# capstone.net
KiCad netlist of a schematic drawn in EAGLE
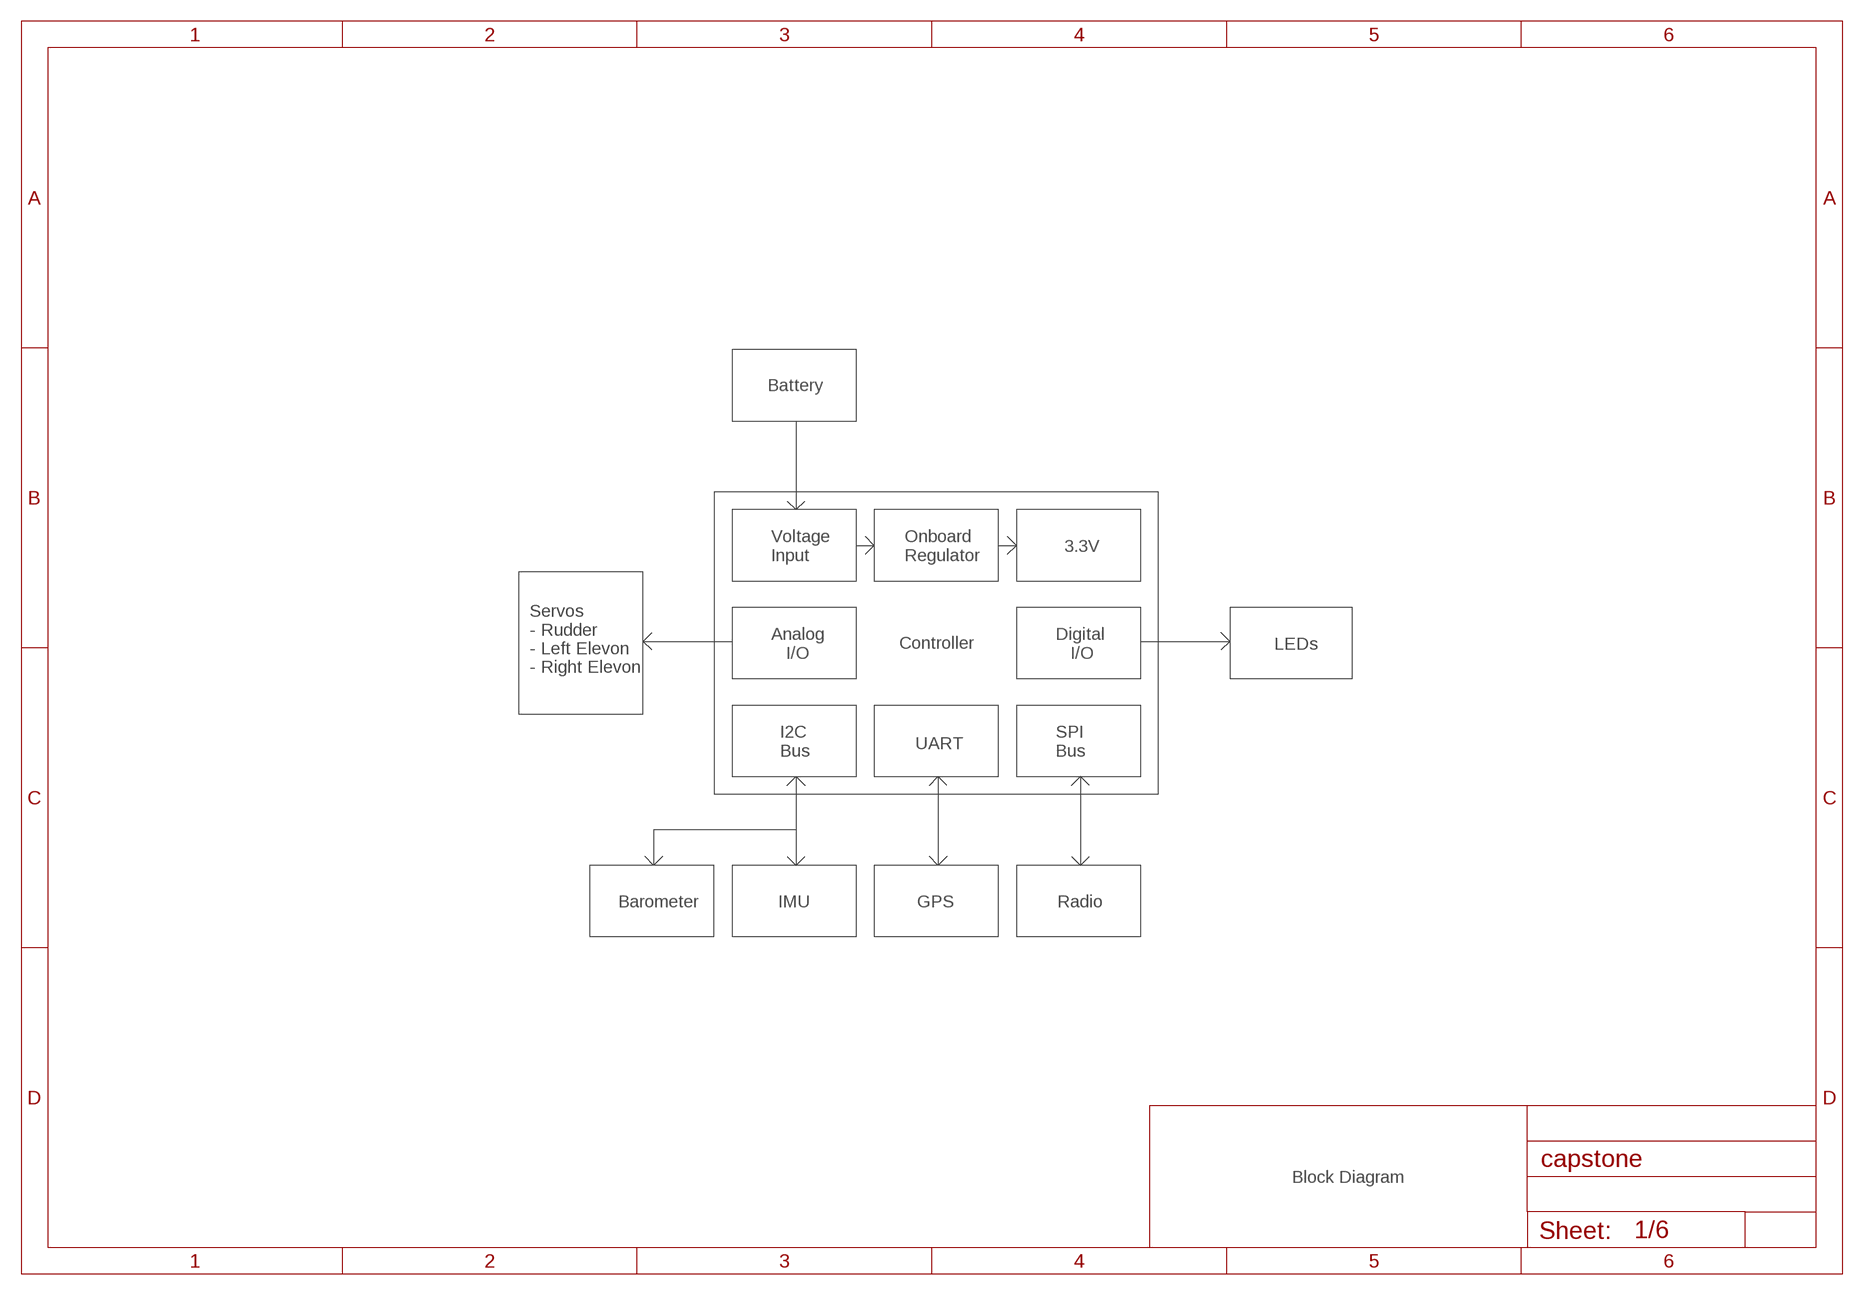
[diagram p0: schematic, sheet 1]
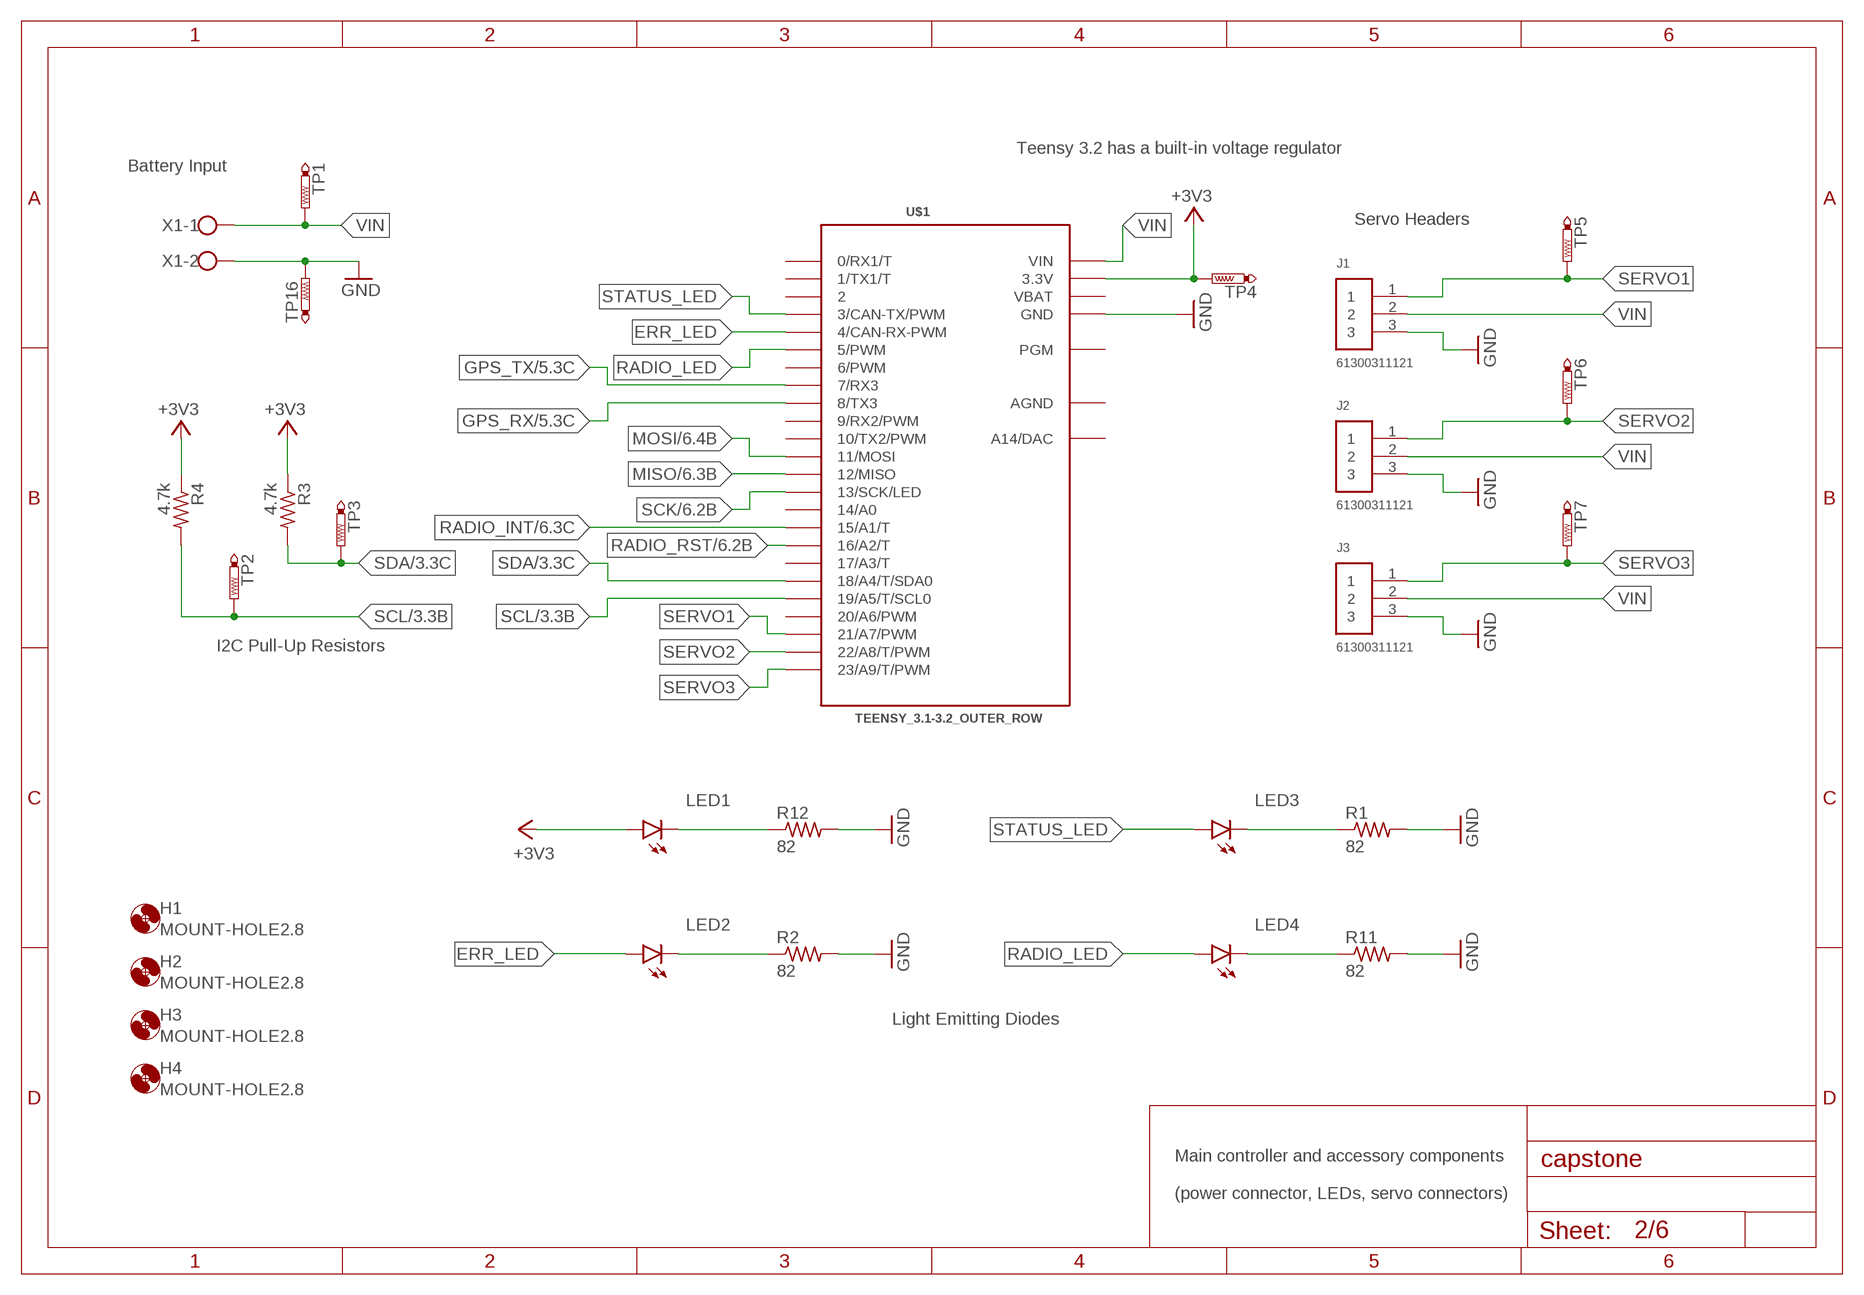
[diagram p1: schematic, sheet 2]
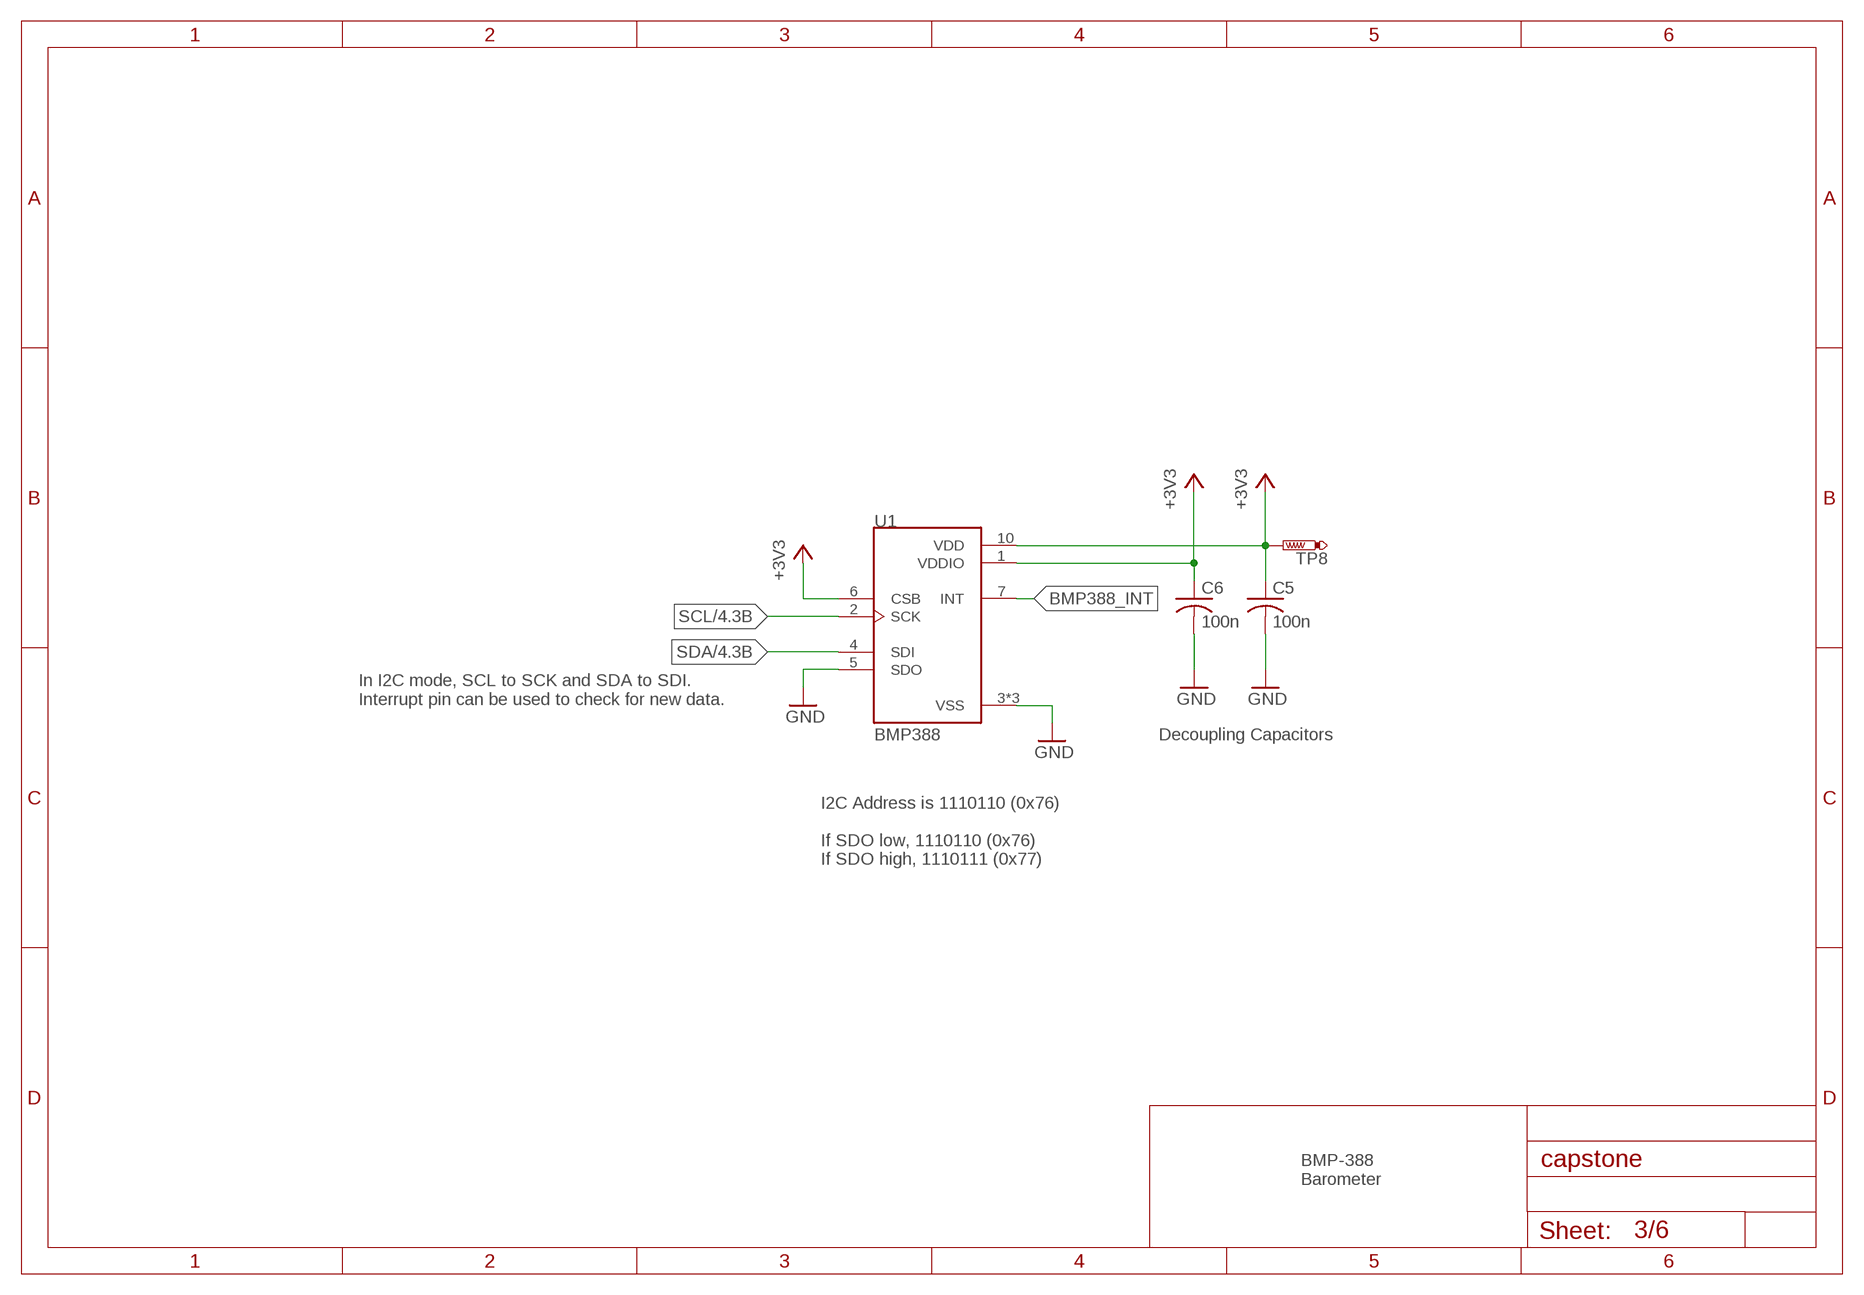
[diagram p2: schematic, sheet 3]
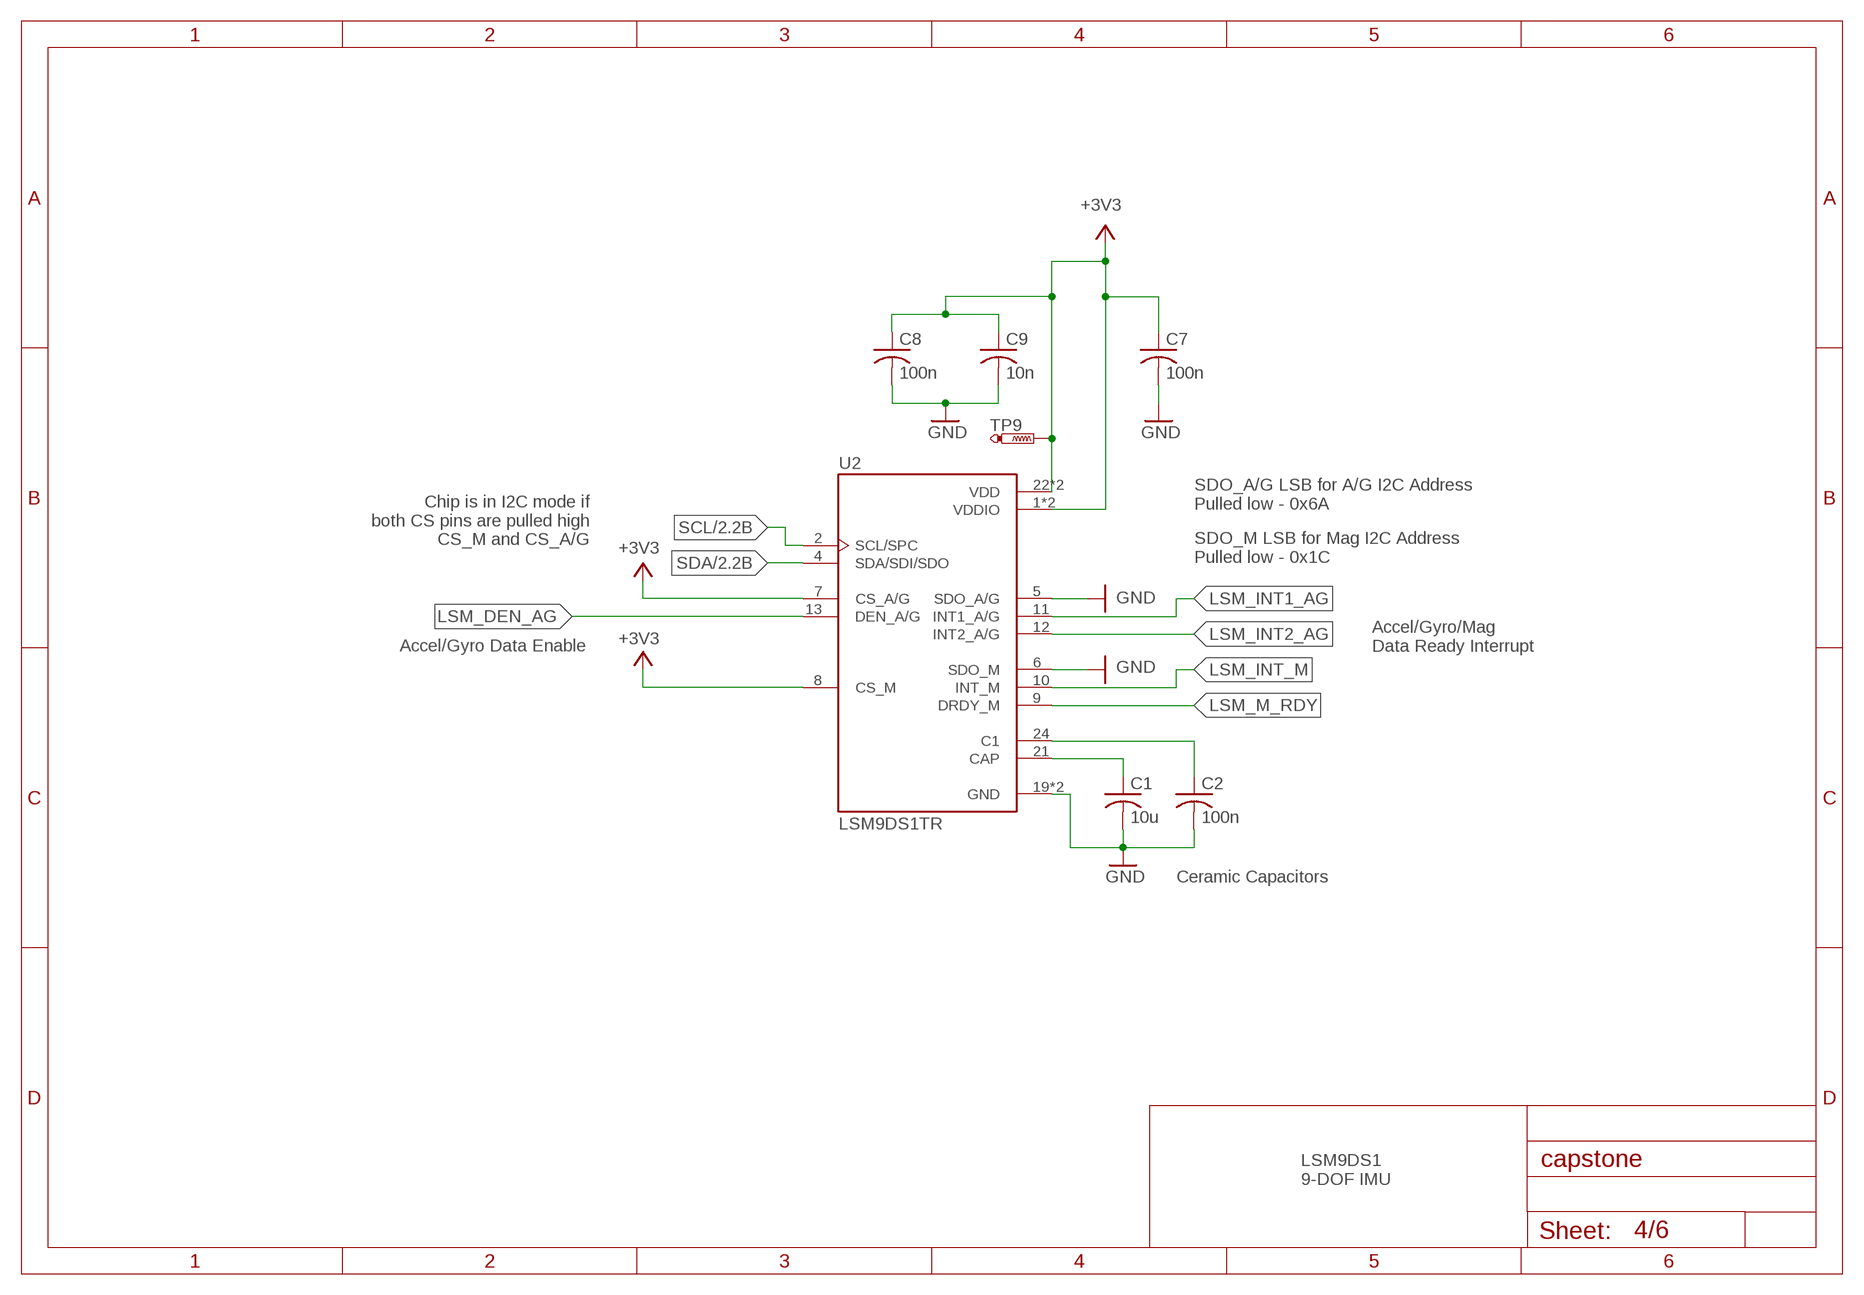
[diagram p3: schematic, sheet 4]
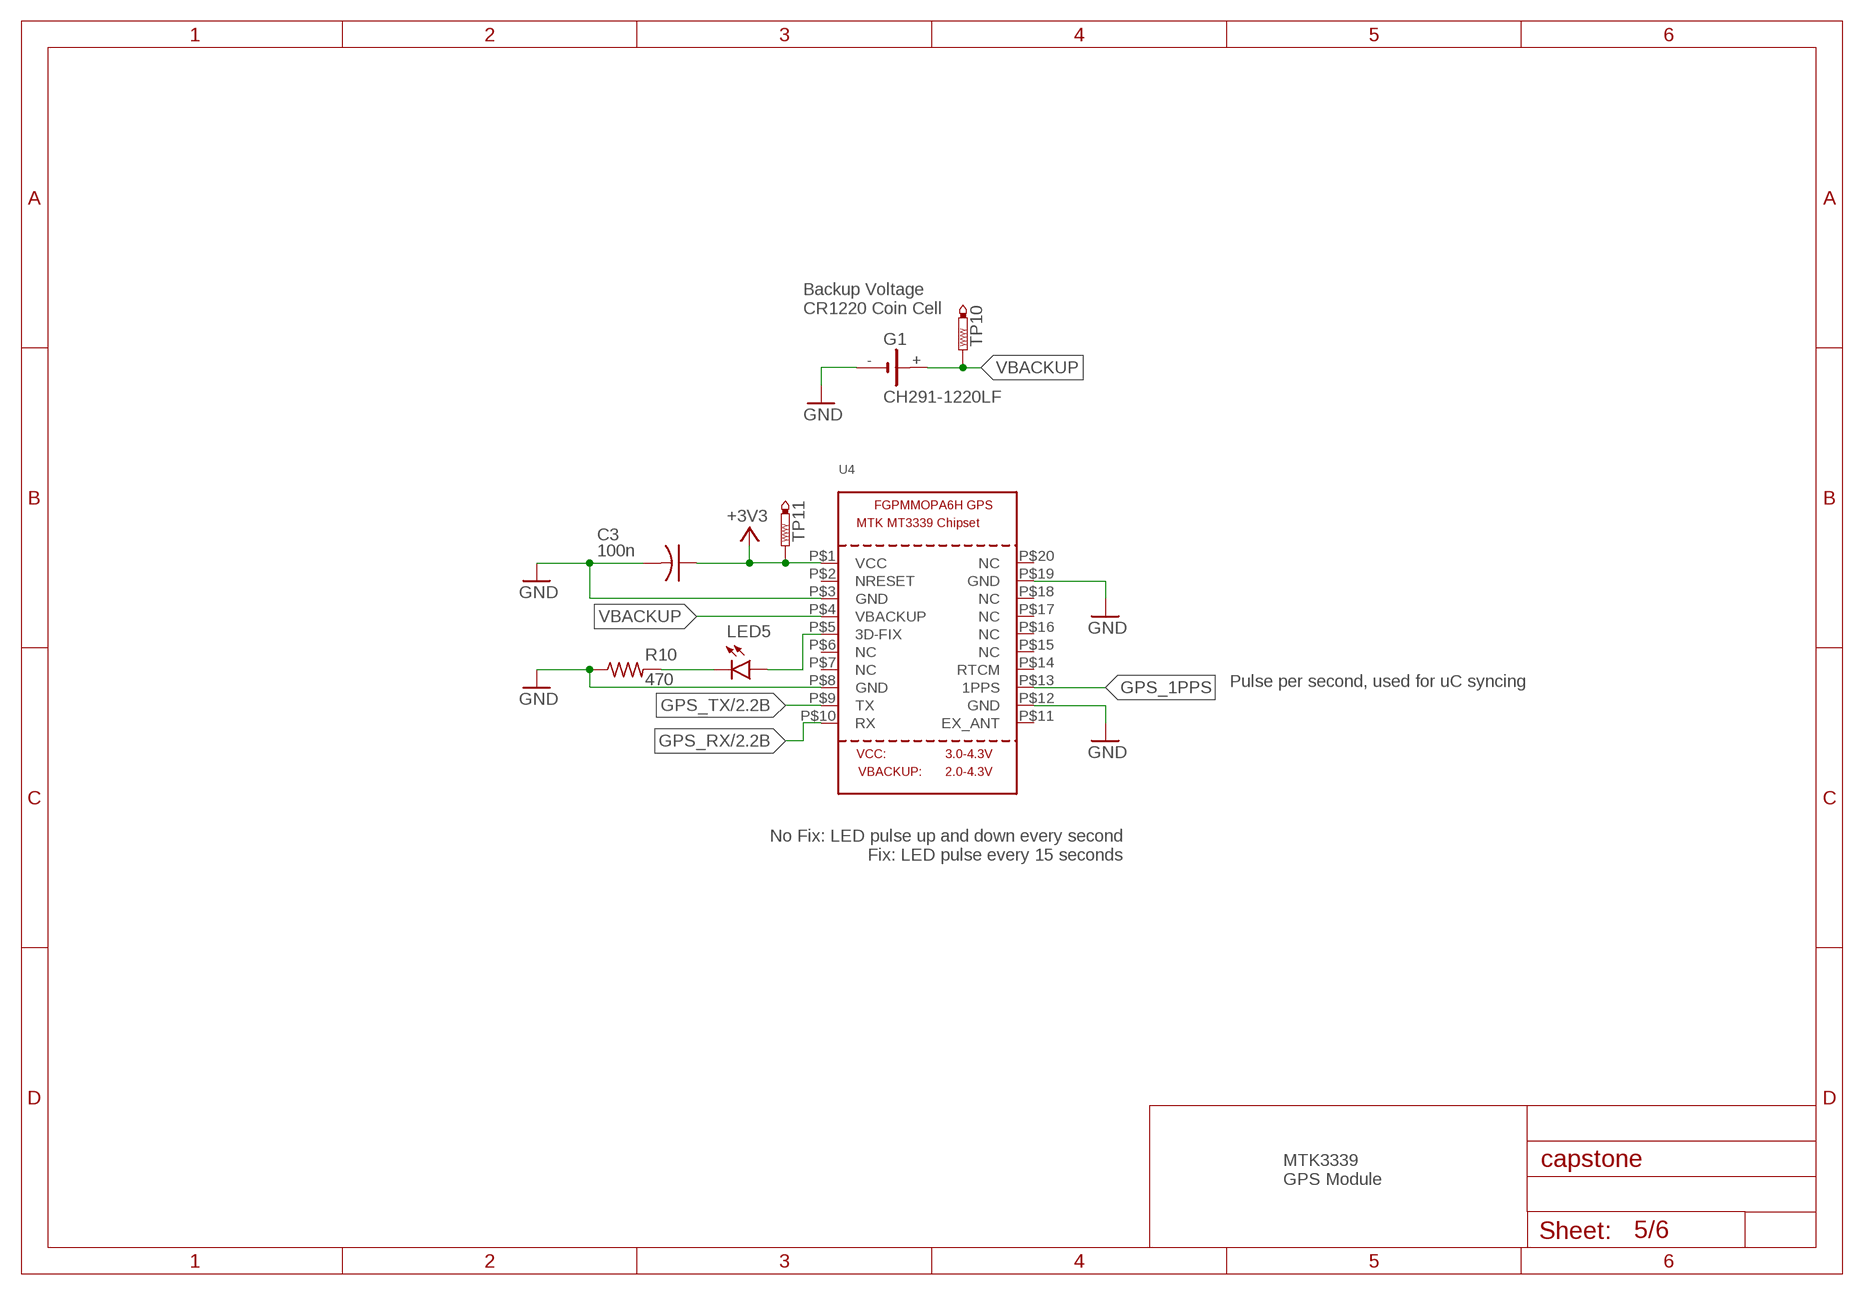
[diagram p4: schematic, sheet 5]
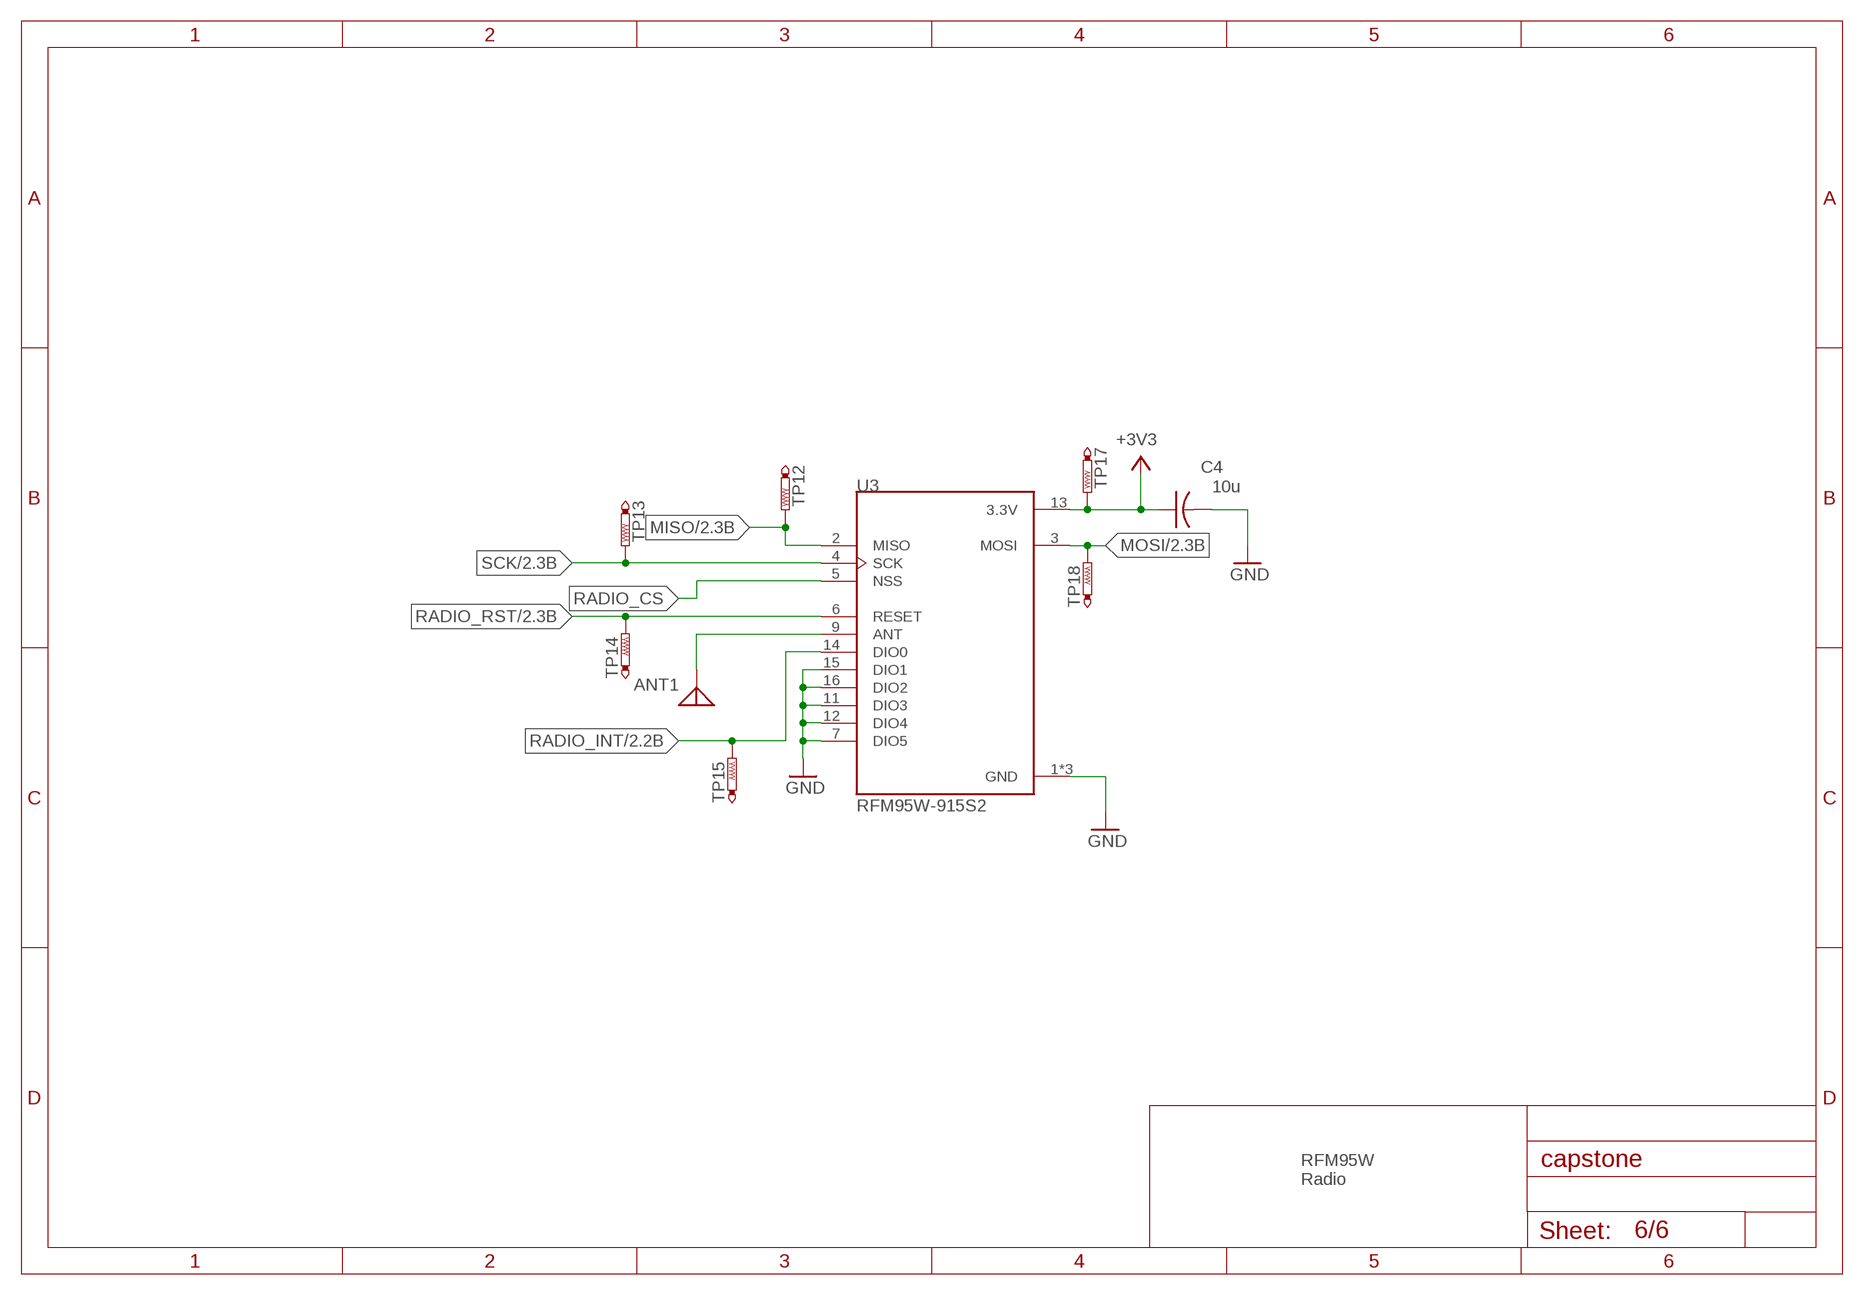
[diagram p5: schematic, sheet 6]

(export (version "E")
  (design (tool "Eeschema 10.0.6"))
  (components
    (comp (ref "C3")
      (value "100n")
      (footprint "eagle-import:C0603")
      (libsource (lib "eagle-import") (part "resistor_348_C-USC0603"))
    )
    (comp (ref "G1")
      (value "CH291-1220LF")
      (footprint "eagle-import:CH291-1220LF")
      (libsource (lib "eagle-import") (part "CH291-1220LF"))
    )
    (comp (ref "LED5")
      (value "HSMH-C190")
      (footprint "eagle-import:LED-0603")
      (fields
        (field (name "DIGIKEY_PART_NUMBER") "516-1420-1-ND")
        (field (name "MANUFACTURER") "Broadcom Limited")
        (field (name "CREATED_BY") "PCBLayout.com")
      )
      (libsource (lib "eagle-import") (part "HSMH-C190"))
    )
    (comp (ref "R10")
      (value "470")
      (footprint "eagle-import:R0603")
      (libsource (lib "eagle-import") (part "R-US_R0603"))
    )
    (comp (ref "TP10")
      (value "PTR1B1,27")
      (footprint "eagle-import:B1,27")
      (libsource (lib "eagle-import") (part "PTR1B1,27"))
    )
    (comp (ref "TP11")
      (value "PTR1B1,27")
      (footprint "eagle-import:B1,27")
      (libsource (lib "eagle-import") (part "PTR1B1,27"))
    )
    (comp (ref "U4")
      (value "GPS_FGPMMOPA6H")
      (footprint "eagle-import:FGPMMOPA6H")
      (libsource (lib "eagle-import") (part "GPS_FGPMMOPA6H"))
    )
    (comp (ref "C1")
      (value "10u")
      (footprint "eagle-import:C0603")
      (libsource (lib "eagle-import") (part "resistor_348_C-USC0603"))
    )
    (comp (ref "C2")
      (value "100n")
      (footprint "eagle-import:C0603")
      (libsource (lib "eagle-import") (part "resistor_348_C-USC0603"))
    )
    (comp (ref "C7")
      (value "100n")
      (footprint "eagle-import:C0603")
      (libsource (lib "eagle-import") (part "resistor_348_C-USC0603"))
    )
    (comp (ref "C8")
      (value "100n")
      (footprint "eagle-import:C0603")
      (libsource (lib "eagle-import") (part "resistor_348_C-USC0603"))
    )
    (comp (ref "C9")
      (value "10n")
      (footprint "eagle-import:C0603")
      (libsource (lib "eagle-import") (part "resistor_348_C-USC0603"))
    )
    (comp (ref "TP9")
      (value "PTR1B1,27")
      (footprint "eagle-import:B1,27")
      (libsource (lib "eagle-import") (part "PTR1B1,27"))
    )
    (comp (ref "U2")
      (value "LSM9DS1TR")
      (footprint "eagle-import:PQFN43P300X350X102-24N")
      (fields (field (name "DIGI-KEY_PART_NUMBER") "497-14946-1-ND") (field (name "MF") "STMicroelectronics"))
      (libsource (lib "eagle-import") (part "LSM9DS1TR"))
    )
    (comp (ref "C5")
      (value "100n")
      (footprint "eagle-import:C0603")
      (libsource (lib "eagle-import") (part "C-USC0603"))
    )
    (comp (ref "C6")
      (value "100n")
      (footprint "eagle-import:C0603")
      (libsource (lib "eagle-import") (part "C-USC0603"))
    )
    (comp (ref "TP8")
      (value "PTR1B1,27")
      (footprint "eagle-import:B1,27")
      (libsource (lib "eagle-import") (part "PTR1B1,27"))
    )
    (comp (ref "U1")
      (value "BMP388")
      (footprint "eagle-import:PQFN50P200X200X80-10N")
      (fields (field (name "DIGI-KEY_PART_NUMBER") "828-1079-1-ND") (field (name "MF") "Bosch Sensortec"))
      (libsource (lib "eagle-import") (part "BMP388"))
    )
    (comp (ref "H1")
      (value "MOUNT-HOLE2.8")
      (footprint "eagle-import:2,8")
      (libsource (lib "eagle-import") (part "MOUNT-HOLE2.8"))
    )
    (comp (ref "H2")
      (value "MOUNT-HOLE2.8")
      (footprint "eagle-import:2,8")
      (libsource (lib "eagle-import") (part "MOUNT-HOLE2.8"))
    )
    (comp (ref "H3")
      (value "MOUNT-HOLE2.8")
      (footprint "eagle-import:2,8")
      (libsource (lib "eagle-import") (part "MOUNT-HOLE2.8"))
    )
    (comp (ref "H4")
      (value "MOUNT-HOLE2.8")
      (footprint "eagle-import:2,8")
      (libsource (lib "eagle-import") (part "MOUNT-HOLE2.8"))
    )
    (comp (ref "J1")
      (value "61300311121")
      (footprint "eagle-import:61300311121")
      (fields
        (field (name "DIGI_KEY_PART_NUMBER") "732-5316-ND")
        (field (name "MANUFACTURER") "Wurth Electronics Inc.")
        (field (name "CREATED_BY") "PCBLayout.com")
      )
      (libsource (lib "eagle-import") (part "61300311121"))
    )
    (comp (ref "J2")
      (value "61300311121")
      (footprint "eagle-import:61300311121")
      (fields
        (field (name "DIGI_KEY_PART_NUMBER") "732-5316-ND")
        (field (name "MANUFACTURER") "Wurth Electronics Inc.")
        (field (name "CREATED_BY") "PCBLayout.com")
      )
      (libsource (lib "eagle-import") (part "61300311121"))
    )
    (comp (ref "J3")
      (value "61300311121")
      (footprint "eagle-import:61300311121")
      (fields
        (field (name "DIGI_KEY_PART_NUMBER") "732-5316-ND")
        (field (name "MANUFACTURER") "Wurth Electronics Inc.")
        (field (name "CREATED_BY") "PCBLayout.com")
      )
      (libsource (lib "eagle-import") (part "61300311121"))
    )
    (comp (ref "LED1")
      (value "HSMH-C190")
      (footprint "eagle-import:LED-0603")
      (fields
        (field (name "DIGIKEY_PART_NUMBER") "516-1420-1-ND")
        (field (name "MANUFACTURER") "Broadcom Limited")
        (field (name "CREATED_BY") "PCBLayout.com")
      )
      (libsource (lib "eagle-import") (part "HSMH-C190"))
    )
    (comp (ref "LED2")
      (value "HSMH-C190")
      (footprint "eagle-import:LED-0603")
      (fields
        (field (name "DIGIKEY_PART_NUMBER") "516-1420-1-ND")
        (field (name "MANUFACTURER") "Broadcom Limited")
        (field (name "CREATED_BY") "PCBLayout.com")
      )
      (libsource (lib "eagle-import") (part "HSMH-C190"))
    )
    (comp (ref "LED3")
      (value "HSMH-C190")
      (footprint "eagle-import:LED-0603")
      (fields
        (field (name "DIGIKEY_PART_NUMBER") "516-1420-1-ND")
        (field (name "MANUFACTURER") "Broadcom Limited")
        (field (name "CREATED_BY") "PCBLayout.com")
      )
      (libsource (lib "eagle-import") (part "HSMH-C190"))
    )
    (comp (ref "LED4")
      (value "HSMH-C190")
      (footprint "eagle-import:LED-0603")
      (fields
        (field (name "DIGIKEY_PART_NUMBER") "516-1420-1-ND")
        (field (name "MANUFACTURER") "Broadcom Limited")
        (field (name "CREATED_BY") "PCBLayout.com")
      )
      (libsource (lib "eagle-import") (part "HSMH-C190"))
    )
    (comp (ref "R1")
      (value "82")
      (footprint "eagle-import:R0603")
      (libsource (lib "eagle-import") (part "R-US_R0603"))
    )
    (comp (ref "R2")
      (value "82")
      (footprint "eagle-import:R0603")
      (libsource (lib "eagle-import") (part "R-US_R0603"))
    )
    (comp (ref "R3")
      (value "4.7k")
      (footprint "eagle-import:R0603")
      (libsource (lib "eagle-import") (part "R-US_R0603"))
    )
    (comp (ref "R4")
      (value "4.7k")
      (footprint "eagle-import:R0603")
      (libsource (lib "eagle-import") (part "R-US_R0603"))
    )
    (comp (ref "R11")
      (value "82")
      (footprint "eagle-import:R0603")
      (libsource (lib "eagle-import") (part "R-US_R0603"))
    )
    (comp (ref "R12")
      (value "82")
      (footprint "eagle-import:R0603")
      (libsource (lib "eagle-import") (part "R-US_R0603"))
    )
    (comp (ref "TP1")
      (value "PTR1B1,27")
      (footprint "eagle-import:B1,27")
      (libsource (lib "eagle-import") (part "PTR1B1,27"))
    )
    (comp (ref "TP2")
      (value "PTR1B1,27")
      (footprint "eagle-import:B1,27")
      (libsource (lib "eagle-import") (part "PTR1B1,27"))
    )
    (comp (ref "TP3")
      (value "PTR1B1,27")
      (footprint "eagle-import:B1,27")
      (libsource (lib "eagle-import") (part "PTR1B1,27"))
    )
    (comp (ref "TP4")
      (value "PTR1B1,27")
      (footprint "eagle-import:B1,27")
      (libsource (lib "eagle-import") (part "PTR1B1,27"))
    )
    (comp (ref "TP5")
      (value "PTR1B1,27")
      (footprint "eagle-import:B1,27")
      (libsource (lib "eagle-import") (part "PTR1B1,27"))
    )
    (comp (ref "TP6")
      (value "PTR1B1,27")
      (footprint "eagle-import:B1,27")
      (libsource (lib "eagle-import") (part "PTR1B1,27"))
    )
    (comp (ref "TP7")
      (value "PTR1B1,27")
      (footprint "eagle-import:B1,27")
      (libsource (lib "eagle-import") (part "PTR1B1,27"))
    )
    (comp (ref "TP16")
      (value "PTR1B1,27")
      (footprint "eagle-import:B1,27")
      (libsource (lib "eagle-import") (part "PTR1B1,27"))
    )
    (comp (ref "U$1")
      (value "TEENSY_3.1-3.2_OUTER_ROW")
      (footprint "eagle-import:TEENSY_3.0-3.2&LC_OUTER_ROW")
      (libsource (lib "eagle-import") (part "TEENSY_3.1-3.2_OUTER_ROW"))
    )
    (comp (ref "X1")
      (value "W237-102")
      (footprint "eagle-import:W237-102")
      (fields (field (name "MPN") "237-102"))
      (libsource (lib "eagle-import") (part "W237-102"))
    )
    (comp (ref "ANT1")
      (value "ANTENNA")
      (footprint "eagle-import:PAD-01")
      (libsource (lib "eagle-import") (part "ANTENNA"))
    )
    (comp (ref "C4")
      (value "10u")
      (footprint "eagle-import:C0603")
      (libsource (lib "eagle-import") (part "resistor_348_C-USC0603"))
    )
    (comp (ref "TP12")
      (value "PTR1B1,27")
      (footprint "eagle-import:B1,27")
      (libsource (lib "eagle-import") (part "PTR1B1,27"))
    )
    (comp (ref "TP13")
      (value "PTR1B1,27")
      (footprint "eagle-import:B1,27")
      (libsource (lib "eagle-import") (part "PTR1B1,27"))
    )
    (comp (ref "TP14")
      (value "PTR1B1,27")
      (footprint "eagle-import:B1,27")
      (libsource (lib "eagle-import") (part "PTR1B1,27"))
    )
    (comp (ref "TP15")
      (value "PTR1B1,27")
      (footprint "eagle-import:B1,27")
      (libsource (lib "eagle-import") (part "PTR1B1,27"))
    )
    (comp (ref "TP17")
      (value "PTR1B1,27")
      (footprint "eagle-import:B1,27")
      (libsource (lib "eagle-import") (part "PTR1B1,27"))
    )
    (comp (ref "TP18")
      (value "PTR1B1,27")
      (footprint "eagle-import:B1,27")
      (libsource (lib "eagle-import") (part "PTR1B1,27"))
    )
    (comp (ref "U3")
      (value "RFM95W-915S2")
      (footprint "eagle-import:XCVR_RFM95W-915S2")
      (fields (field (name "DIGI-KEY_PART_NUMBER") "RFM95W-915S2-ND") (field (name "MF") "RF Solutions"))
      (libsource (lib "eagle-import") (part "RFM95W-915S2"))
    )
  )
  (nets
    (net (code "1") (name "+3V3") (class "Default")
      (node (ref "C3") (pin "1") (pinfunction "1_1") (pintype "passive"))
      (node (ref "C4") (pin "1") (pinfunction "1_1") (pintype "passive"))
      (node (ref "C5") (pin "1") (pinfunction "1_1") (pintype "passive"))
      (node (ref "C6") (pin "1") (pinfunction "1_1") (pintype "passive"))
      (node (ref "C7") (pin "1") (pinfunction "1_1") (pintype "passive"))
      (node (ref "C8") (pin "1") (pinfunction "1_1") (pintype "passive"))
      (node (ref "C9") (pin "1") (pinfunction "1_1") (pintype "passive"))
      (node (ref "LED1") (pin "A") (pinfunction "A_A") (pintype "passive"))
      (node (ref "R3") (pin "1") (pinfunction "1_1") (pintype "passive"))
      (node (ref "R4") (pin "1") (pinfunction "1_1") (pintype "passive"))
      (node (ref "TP11") (pin "TP") (pinfunction "TP_TP") (pintype "input"))
      (node (ref "TP17") (pin "TP") (pinfunction "TP_TP") (pintype "input"))
      (node (ref "TP4") (pin "TP") (pinfunction "TP_TP") (pintype "input"))
      (node (ref "TP8") (pin "TP") (pinfunction "TP_TP") (pintype "input"))
      (node (ref "TP9") (pin "TP") (pinfunction "TP_TP") (pintype "input"))
      (node (ref "U$1") (pin "3.3V") (pinfunction "3.3V_3.3V") (pintype "power_in"))
      (node (ref "U$1") (pin "3.3V1") (pinfunction "3.3V_3.3V1") (pintype "power_in"))
      (node (ref "U1") (pin "1") (pinfunction "VDDIO_1") (pintype "power_in"))
      (node (ref "U1") (pin "10") (pinfunction "VDD_10") (pintype "power_in"))
      (node (ref "U1") (pin "6") (pinfunction "CSB_6") (pintype "input"))
      (node (ref "U2") (pin "1") (pinfunction "VDDIO_1") (pintype "power_in"))
      (node (ref "U2") (pin "22") (pinfunction "VDD_22") (pintype "power_in"))
      (node (ref "U2") (pin "23") (pinfunction "VDD_23") (pintype "power_in"))
      (node (ref "U2") (pin "3") (pinfunction "VDDIO_3") (pintype "power_in"))
      (node (ref "U2") (pin "7") (pinfunction "CS_A/G_7") (pintype "input"))
      (node (ref "U2") (pin "8") (pinfunction "CS_M_8") (pintype "input"))
      (node (ref "U3") (pin "13") (pinfunction "3.3V_13") (pintype "power_in"))
      (node (ref "U4") (pin "P$1") (pinfunction "VCC_P$1") (pintype "bidirectional"))
    )
    (net (code "2") (name "AGND") (class "Default")
      (node (ref "U$1") (pin "AGND") (pinfunction "AGND_AGND") (pintype "power_in"))
    )
    (net (code "3") (name "BMP388_INT") (class "Default")
      (node (ref "U1") (pin "7") (pinfunction "INT_7") (pintype "output"))
    )
    (net (code "4") (name "ERR_LED") (class "Default")
      (node (ref "LED2") (pin "A") (pinfunction "A_A") (pintype "passive"))
      (node (ref "U$1") (pin "4") (pinfunction "4/CAN-RX-PWM_4") (pintype "bidirectional"))
    )
    (net (code "5") (name "GND") (class "Default")
      (node (ref "C1") (pin "2") (pinfunction "2_2") (pintype "passive"))
      (node (ref "C2") (pin "2") (pinfunction "2_2") (pintype "passive"))
      (node (ref "C3") (pin "2") (pinfunction "2_2") (pintype "passive"))
      (node (ref "C4") (pin "2") (pinfunction "2_2") (pintype "passive"))
      (node (ref "C5") (pin "2") (pinfunction "2_2") (pintype "passive"))
      (node (ref "C6") (pin "2") (pinfunction "2_2") (pintype "passive"))
      (node (ref "C7") (pin "2") (pinfunction "2_2") (pintype "passive"))
      (node (ref "C8") (pin "2") (pinfunction "2_2") (pintype "passive"))
      (node (ref "C9") (pin "2") (pinfunction "2_2") (pintype "passive"))
      (node (ref "G1") (pin "-") (pinfunction "-_-") (pintype "passive"))
      (node (ref "J1") (pin "3") (pinfunction "3_3") (pintype "passive"))
      (node (ref "J2") (pin "3") (pinfunction "3_3") (pintype "passive"))
      (node (ref "J3") (pin "3") (pinfunction "3_3") (pintype "passive"))
      (node (ref "R1") (pin "2") (pinfunction "2_2") (pintype "passive"))
      (node (ref "R10") (pin "1") (pinfunction "1_1") (pintype "passive"))
      (node (ref "R11") (pin "2") (pinfunction "2_2") (pintype "passive"))
      (node (ref "R12") (pin "2") (pinfunction "2_2") (pintype "passive"))
      (node (ref "R2") (pin "2") (pinfunction "2_2") (pintype "passive"))
      (node (ref "TP16") (pin "TP") (pinfunction "TP_TP") (pintype "input"))
      (node (ref "U$1") (pin "GND") (pinfunction "GND_GND") (pintype "power_in"))
      (node (ref "U$1") (pin "GND1") (pinfunction "GND_GND1") (pintype "power_in"))
      (node (ref "U1") (pin "3") (pinfunction "VSS_3") (pintype "power_in"))
      (node (ref "U1") (pin "5") (pinfunction "SDO_5") (pintype "bidirectional"))
      (node (ref "U1") (pin "8") (pinfunction "VSS_8") (pintype "power_in"))
      (node (ref "U1") (pin "9") (pinfunction "VSS_9") (pintype "power_in"))
      (node (ref "U2") (pin "19") (pinfunction "GND_19") (pintype "power_in"))
      (node (ref "U2") (pin "20") (pinfunction "GND_20") (pintype "power_in"))
      (node (ref "U2") (pin "5") (pinfunction "SDO_A/G_5") (pintype "output"))
      (node (ref "U2") (pin "6") (pinfunction "SDO_M_6") (pintype "output"))
      (node (ref "U3") (pin "1") (pinfunction "GND_1") (pintype "power_in"))
      (node (ref "U3") (pin "10") (pinfunction "GND_10") (pintype "power_in"))
      (node (ref "U3") (pin "11") (pinfunction "DIO3_11") (pintype "bidirectional"))
      (node (ref "U3") (pin "12") (pinfunction "DIO4_12") (pintype "bidirectional"))
      (node (ref "U3") (pin "15") (pinfunction "DIO1_15") (pintype "bidirectional"))
      (node (ref "U3") (pin "16") (pinfunction "DIO2_16") (pintype "bidirectional"))
      (node (ref "U3") (pin "7") (pinfunction "DIO5_7") (pintype "bidirectional"))
      (node (ref "U3") (pin "8") (pinfunction "GND_8") (pintype "power_in"))
      (node (ref "U4") (pin "P$12") (pinfunction "GND_P$12") (pintype "bidirectional"))
      (node (ref "U4") (pin "P$19") (pinfunction "GND_P$19") (pintype "bidirectional"))
      (node (ref "U4") (pin "P$3") (pinfunction "GND_P$3") (pintype "bidirectional"))
      (node (ref "U4") (pin "P$8") (pinfunction "GND_P$8") (pintype "bidirectional"))
      (node (ref "X1") (pin "2") (pinfunction "KL_2") (pintype "passive"))
    )
    (net (code "6") (name "GPS_1PPS") (class "Default")
      (node (ref "U4") (pin "P$13") (pinfunction "1PPS_P$13") (pintype "bidirectional"))
    )
    (net (code "7") (name "GPS_RX") (class "Default")
      (node (ref "U$1") (pin "8") (pinfunction "8/TX3_8") (pintype "bidirectional"))
      (node (ref "U4") (pin "P$10") (pinfunction "RX_P$10") (pintype "bidirectional"))
    )
    (net (code "8") (name "GPS_TX") (class "Default")
      (node (ref "U$1") (pin "7") (pinfunction "7/RX3_7") (pintype "bidirectional"))
      (node (ref "U4") (pin "P$9") (pinfunction "TX_P$9") (pintype "bidirectional"))
    )
    (net (code "9") (name "LSM_DEN_AG") (class "Default")
      (node (ref "U2") (pin "13") (pinfunction "DEN_A/G_13") (pintype "input"))
    )
    (net (code "10") (name "LSM_INT1_AG") (class "Default")
      (node (ref "U2") (pin "11") (pinfunction "INT1_A/G_11") (pintype "output"))
    )
    (net (code "11") (name "LSM_INT2_AG") (class "Default")
      (node (ref "U2") (pin "12") (pinfunction "INT2_A/G_12") (pintype "output"))
    )
    (net (code "12") (name "LSM_INT_M") (class "Default")
      (node (ref "U2") (pin "10") (pinfunction "INT_M_10") (pintype "output"))
    )
    (net (code "13") (name "LSM_M_RDY") (class "Default")
      (node (ref "U2") (pin "9") (pinfunction "DRDY_M_9") (pintype "output"))
    )
    (net (code "14") (name "MISO") (class "Default")
      (node (ref "TP12") (pin "TP") (pinfunction "TP_TP") (pintype "input"))
      (node (ref "U$1") (pin "12") (pinfunction "12/MISO_12") (pintype "bidirectional"))
      (node (ref "U3") (pin "2") (pinfunction "MISO_2") (pintype "input"))
    )
    (net (code "15") (name "MOSI") (class "Default")
      (node (ref "TP18") (pin "TP") (pinfunction "TP_TP") (pintype "input"))
      (node (ref "U$1") (pin "11") (pinfunction "11/MOSI_11") (pintype "bidirectional"))
      (node (ref "U3") (pin "3") (pinfunction "MOSI_3") (pintype "output"))
    )
    (net (code "16") (name "Net-(LED1-PadC)") (class "Default")
      (node (ref "LED1") (pin "C") (pinfunction "C_C") (pintype "passive"))
      (node (ref "R12") (pin "1") (pinfunction "1_1") (pintype "passive"))
    )
    (net (code "17") (name "Net-(LED2-PadC)") (class "Default")
      (node (ref "LED2") (pin "C") (pinfunction "C_C") (pintype "passive"))
      (node (ref "R2") (pin "1") (pinfunction "1_1") (pintype "passive"))
    )
    (net (code "18") (name "Net-(LED3-PadC)") (class "Default")
      (node (ref "LED3") (pin "C") (pinfunction "C_C") (pintype "passive"))
      (node (ref "R1") (pin "1") (pinfunction "1_1") (pintype "passive"))
    )
    (net (code "19") (name "Net-(LED4-PadC)") (class "Default")
      (node (ref "LED4") (pin "C") (pinfunction "C_C") (pintype "passive"))
      (node (ref "R11") (pin "1") (pinfunction "1_1") (pintype "passive"))
    )
    (net (code "20") (name "Net-(LED5-PadC)") (class "Default")
      (node (ref "LED5") (pin "C") (pinfunction "C_C") (pintype "passive"))
      (node (ref "R10") (pin "2") (pinfunction "2_2") (pintype "passive"))
    )
    (net (code "21") (name "Net-(U2-C1)") (class "Default")
      (node (ref "C2") (pin "1") (pinfunction "1_1") (pintype "passive"))
      (node (ref "U2") (pin "24") (pinfunction "C1_24") (pintype "passive"))
    )
    (net (code "22") (name "Net-(U2-CAP)") (class "Default")
      (node (ref "C1") (pin "1") (pinfunction "1_1") (pintype "passive"))
      (node (ref "U2") (pin "21") (pinfunction "CAP_21") (pintype "passive"))
    )
    (net (code "23") (name "Net-(U3-ANT)") (class "Default")
      (node (ref "ANT1") (pin "1") (pinfunction "1_1") (pintype "output"))
      (node (ref "U3") (pin "9") (pinfunction "ANT_9") (pintype "bidirectional"))
    )
    (net (code "24") (name "Net-(U4-3D-FIX)") (class "Default")
      (node (ref "LED5") (pin "A") (pinfunction "A_A") (pintype "passive"))
      (node (ref "U4") (pin "P$5") (pinfunction "3D-FIX_P$5") (pintype "bidirectional"))
    )
    (net (code "25") (name "RADIO_CS") (class "Default")
      (node (ref "U3") (pin "5") (pinfunction "NSS_5") (pintype "input"))
    )
    (net (code "26") (name "RADIO_INT") (class "Default")
      (node (ref "TP15") (pin "TP") (pinfunction "TP_TP") (pintype "input"))
      (node (ref "U$1") (pin "15/A1") (pinfunction "15/A1/T_15/A1") (pintype "bidirectional"))
      (node (ref "U3") (pin "14") (pinfunction "DIO0_14") (pintype "bidirectional"))
    )
    (net (code "27") (name "RADIO_LED") (class "Default")
      (node (ref "LED4") (pin "A") (pinfunction "A_A") (pintype "passive"))
      (node (ref "U$1") (pin "5") (pinfunction "5/PWM_5") (pintype "bidirectional"))
    )
    (net (code "28") (name "RADIO_RST") (class "Default")
      (node (ref "TP14") (pin "TP") (pinfunction "TP_TP") (pintype "input"))
      (node (ref "U$1") (pin "16/A2") (pinfunction "16/A2/T_16/A2") (pintype "bidirectional"))
      (node (ref "U3") (pin "6") (pinfunction "RESET_6") (pintype "bidirectional"))
    )
    (net (code "29") (name "SCK") (class "Default")
      (node (ref "TP13") (pin "TP") (pinfunction "TP_TP") (pintype "input"))
      (node (ref "U$1") (pin "13") (pinfunction "13/SCK/LED_13") (pintype "bidirectional"))
      (node (ref "U3") (pin "4") (pinfunction "SCK_4") (pintype "input"))
    )
    (net (code "30") (name "SCL") (class "Default")
      (node (ref "R4") (pin "2") (pinfunction "2_2") (pintype "passive"))
      (node (ref "TP2") (pin "TP") (pinfunction "TP_TP") (pintype "input"))
      (node (ref "U$1") (pin "19/A5") (pinfunction "19/A5/T/SCL0_19/A5") (pintype "bidirectional"))
      (node (ref "U1") (pin "2") (pinfunction "SCK_2") (pintype "input"))
      (node (ref "U2") (pin "2") (pinfunction "SCL/SPC_2") (pintype "input"))
    )
    (net (code "31") (name "SDA") (class "Default")
      (node (ref "R3") (pin "2") (pinfunction "2_2") (pintype "passive"))
      (node (ref "TP3") (pin "TP") (pinfunction "TP_TP") (pintype "input"))
      (node (ref "U$1") (pin "18/A4") (pinfunction "18/A4/T/SDA0_18/A4") (pintype "bidirectional"))
      (node (ref "U1") (pin "4") (pinfunction "SDI_4") (pintype "bidirectional"))
      (node (ref "U2") (pin "4") (pinfunction "SDA/SDI/SDO_4") (pintype "bidirectional"))
    )
    (net (code "32") (name "SERVO1") (class "Default")
      (node (ref "J1") (pin "1") (pinfunction "1_1") (pintype "passive"))
      (node (ref "TP5") (pin "TP") (pinfunction "TP_TP") (pintype "input"))
      (node (ref "U$1") (pin "21/A7") (pinfunction "21/A7/PWM_21/A7") (pintype "bidirectional"))
    )
    (net (code "33") (name "SERVO2") (class "Default")
      (node (ref "J2") (pin "1") (pinfunction "1_1") (pintype "passive"))
      (node (ref "TP6") (pin "TP") (pinfunction "TP_TP") (pintype "input"))
      (node (ref "U$1") (pin "22/A8") (pinfunction "22/A8/T/PWM_22/A8") (pintype "bidirectional"))
    )
    (net (code "34") (name "SERVO3") (class "Default")
      (node (ref "J3") (pin "1") (pinfunction "1_1") (pintype "passive"))
      (node (ref "TP7") (pin "TP") (pinfunction "TP_TP") (pintype "input"))
      (node (ref "U$1") (pin "23/A9") (pinfunction "23/A9/T/PWM_23/A9") (pintype "bidirectional"))
    )
    (net (code "35") (name "STATUS_LED") (class "Default")
      (node (ref "LED3") (pin "A") (pinfunction "A_A") (pintype "passive"))
      (node (ref "U$1") (pin "3") (pinfunction "3/CAN-TX/PWM_3") (pintype "bidirectional"))
    )
    (net (code "36") (name "VBACKUP") (class "Default")
      (node (ref "G1") (pin "+") (pinfunction "+_+") (pintype "passive"))
      (node (ref "TP10") (pin "TP") (pinfunction "TP_TP") (pintype "input"))
      (node (ref "U4") (pin "P$4") (pinfunction "VBACKUP_P$4") (pintype "bidirectional"))
    )
    (net (code "37") (name "VBAT") (class "Default")
      (node (ref "U$1") (pin "VBAT") (pinfunction "VBAT_VBAT") (pintype "power_in"))
    )
    (net (code "38") (name "VIN") (class "Default")
      (node (ref "J1") (pin "2") (pinfunction "2_2") (pintype "passive"))
      (node (ref "J2") (pin "2") (pinfunction "2_2") (pintype "passive"))
      (node (ref "J3") (pin "2") (pinfunction "2_2") (pintype "passive"))
      (node (ref "TP1") (pin "TP") (pinfunction "TP_TP") (pintype "input"))
      (node (ref "U$1") (pin "VIN") (pinfunction "VIN_VIN") (pintype "power_in"))
      (node (ref "X1") (pin "1") (pinfunction "KL_1") (pintype "passive"))
    )
    (net (code "39") (name "unconnected-(U$1-0{slash}RX1{slash}T-Pad0)") (class "Default")
      (node (ref "U$1") (pin "0") (pinfunction "0/RX1/T_0") (pintype "bidirectional"))
    )
    (net (code "40") (name "unconnected-(U$1-1{slash}TX1{slash}T-Pad1)") (class "Default")
      (node (ref "U$1") (pin "1") (pinfunction "1/TX1/T_1") (pintype "bidirectional"))
    )
    (net (code "41") (name "unconnected-(U$1-6{slash}PWM-Pad6)") (class "Default")
      (node (ref "U$1") (pin "6") (pinfunction "6/PWM_6") (pintype "bidirectional"))
    )
    (net (code "42") (name "unconnected-(U$1-9{slash}RX2{slash}PWM-Pad9)") (class "Default")
      (node (ref "U$1") (pin "9") (pinfunction "9/RX2/PWM_9") (pintype "bidirectional"))
    )
    (net (code "43") (name "unconnected-(U$1-10{slash}TX2{slash}PWM-Pad10)") (class "Default")
      (node (ref "U$1") (pin "10") (pinfunction "10/TX2/PWM_10") (pintype "bidirectional"))
    )
    (net (code "44") (name "unconnected-(U$1-17{slash}A3{slash}T-Pad17{slash}A3)") (class "Default")
      (node (ref "U$1") (pin "17/A3") (pinfunction "17/A3/T_17/A3") (pintype "bidirectional"))
    )
    (net (code "45") (name "unconnected-(U$1-20{slash}A6{slash}PWM-Pad20{slash}A6)") (class "Default")
      (node (ref "U$1") (pin "20/A6") (pinfunction "20/A6/PWM_20/A6") (pintype "bidirectional"))
    )
    (net (code "46") (name "unconnected-(U$1-A14{slash}DAC-PadRESET{slash}DAC)") (class "Default")
      (node (ref "U$1") (pin "RESET/DAC") (pinfunction "A14/DAC_RESET/DAC") (pintype "bidirectional"))
    )
    (net (code "47") (name "unconnected-(U$1-Pad2)") (class "Default")
      (node (ref "U$1") (pin "2") (pinfunction "2_2") (pintype "bidirectional"))
    )
    (net (code "48") (name "unconnected-(U$1-Pad14{slash}A0)") (class "Default")
      (node (ref "U$1") (pin "14/A0") (pinfunction "14/A0_14/A0") (pintype "bidirectional"))
    )
    (net (code "49") (name "unconnected-(U$1-PadPGM)") (class "Default")
      (node (ref "U$1") (pin "PGM") (pinfunction "PGM_PGM") (pintype "bidirectional"))
    )
    (net (code "50") (name "unconnected-(U4-EX_ANT-PadP$11)") (class "Default")
      (node (ref "U4") (pin "P$11") (pinfunction "EX_ANT_P$11") (pintype "bidirectional"))
    )
    (net (code "51") (name "unconnected-(U4-NC-PadP$6)") (class "Default")
      (node (ref "U4") (pin "P$6") (pinfunction "NC_P$6") (pintype "bidirectional"))
    )
    (net (code "52") (name "unconnected-(U4-NC-PadP$7)") (class "Default")
      (node (ref "U4") (pin "P$7") (pinfunction "NC_P$7") (pintype "bidirectional"))
    )
    (net (code "53") (name "unconnected-(U4-NC-PadP$15)") (class "Default")
      (node (ref "U4") (pin "P$15") (pinfunction "NC_P$15") (pintype "bidirectional"))
    )
    (net (code "54") (name "unconnected-(U4-NC-PadP$16)") (class "Default")
      (node (ref "U4") (pin "P$16") (pinfunction "NC_P$16") (pintype "bidirectional"))
    )
    (net (code "55") (name "unconnected-(U4-NC-PadP$17)") (class "Default")
      (node (ref "U4") (pin "P$17") (pinfunction "NC_P$17") (pintype "bidirectional"))
    )
    (net (code "56") (name "unconnected-(U4-NC-PadP$18)") (class "Default")
      (node (ref "U4") (pin "P$18") (pinfunction "NC_P$18") (pintype "bidirectional"))
    )
    (net (code "57") (name "unconnected-(U4-NC-PadP$20)") (class "Default")
      (node (ref "U4") (pin "P$20") (pinfunction "NC_P$20") (pintype "bidirectional"))
    )
    (net (code "58") (name "unconnected-(U4-NRESET-PadP$2)") (class "Default")
      (node (ref "U4") (pin "P$2") (pinfunction "NRESET_P$2") (pintype "bidirectional"))
    )
    (net (code "59") (name "unconnected-(U4-RTCM-PadP$14)") (class "Default")
      (node (ref "U4") (pin "P$14") (pinfunction "RTCM_P$14") (pintype "bidirectional"))
    )
  )
)
